# WAB_1x4_bus_transceivers.net
KiCad netlist of a schematic drawn in Altium Designer
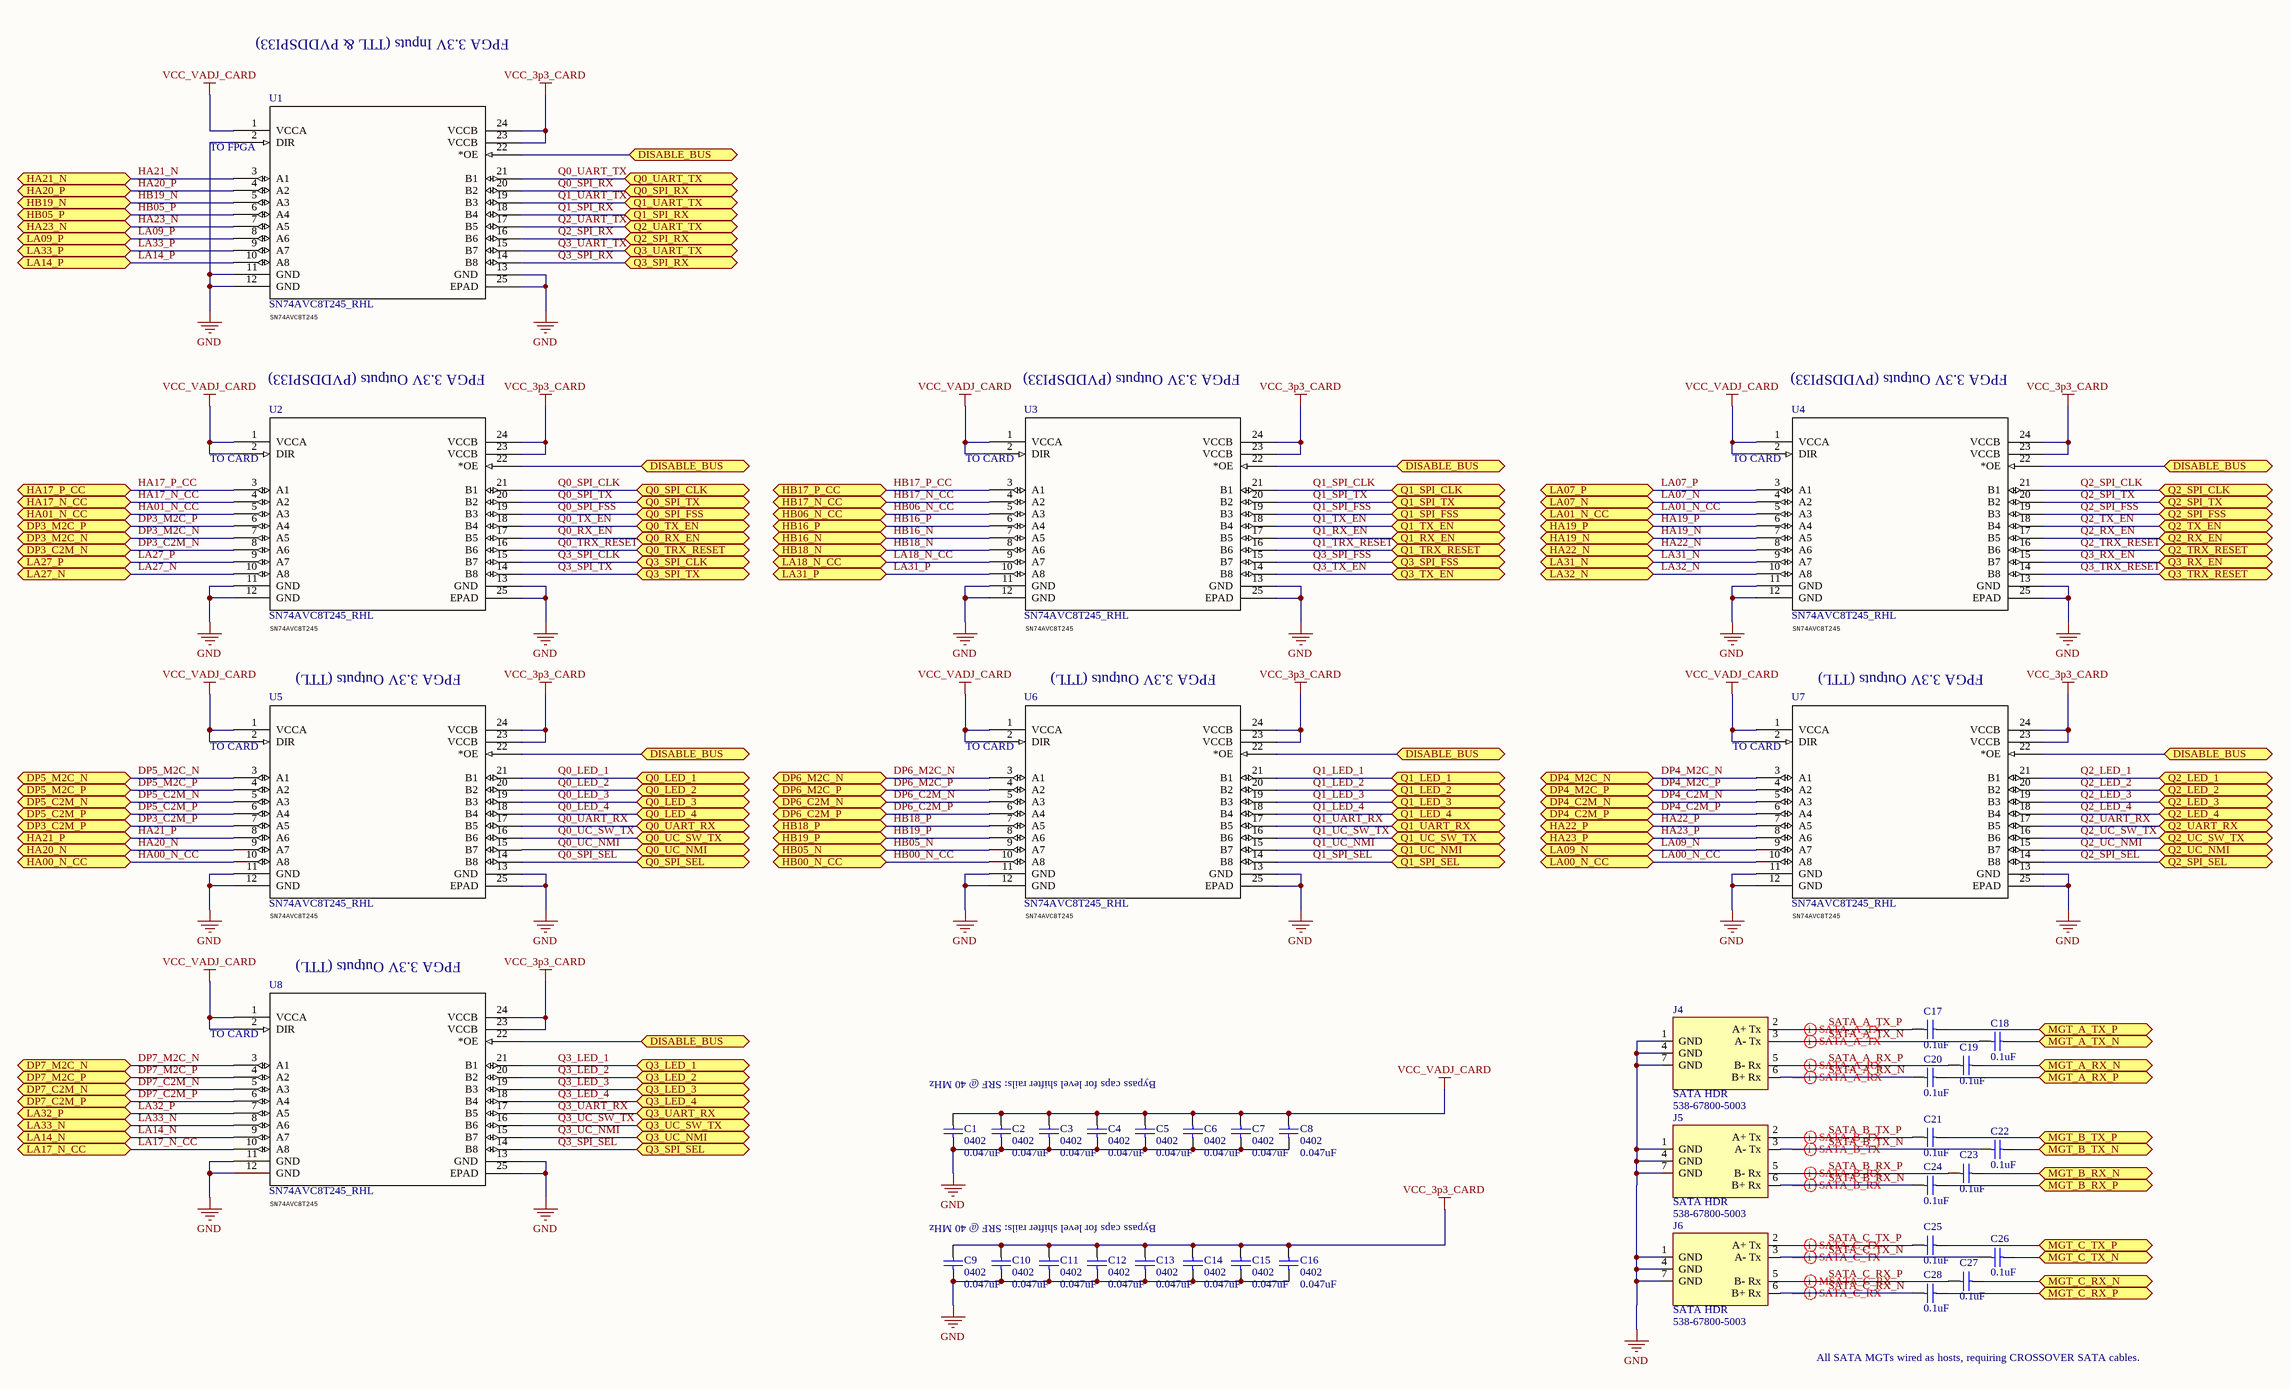
[diagram p0: WAB_1x4_bus_transceivers.SchDoc]

(export (version "E")
  (design (tool "Eeschema 10.0.6"))
  (components
    (comp (ref "C1")
      (value "0402")
      (footprint "0402_SMT_CAP")
      (description "0402 SMT Capacitor")
      (fields (field (name "ALTIUM_VALUE") "0.047uF"))
      (libsource (lib "RNG_Parts") (part "Cap_0402"))
    )
    (comp (ref "C2")
      (value "0402")
      (footprint "0402_SMT_CAP")
      (description "0402 SMT Capacitor")
      (fields (field (name "ALTIUM_VALUE") "0.047uF"))
      (libsource (lib "RNG_Parts") (part "Cap_0402"))
    )
    (comp (ref "C3")
      (value "0402")
      (footprint "0402_SMT_CAP")
      (description "0402 SMT Capacitor")
      (fields (field (name "ALTIUM_VALUE") "0.047uF"))
      (libsource (lib "RNG_Parts") (part "Cap_0402"))
    )
    (comp (ref "C4")
      (value "0402")
      (footprint "0402_SMT_CAP")
      (description "0402 SMT Capacitor")
      (fields (field (name "ALTIUM_VALUE") "0.047uF"))
      (libsource (lib "RNG_Parts") (part "Cap_0402"))
    )
    (comp (ref "C5")
      (value "0402")
      (footprint "0402_SMT_CAP")
      (description "0402 SMT Capacitor")
      (fields (field (name "ALTIUM_VALUE") "0.047uF"))
      (libsource (lib "RNG_Parts") (part "Cap_0402"))
    )
    (comp (ref "C6")
      (value "0402")
      (footprint "0402_SMT_CAP")
      (description "0402 SMT Capacitor")
      (fields (field (name "ALTIUM_VALUE") "0.047uF"))
      (libsource (lib "RNG_Parts") (part "Cap_0402"))
    )
    (comp (ref "C7")
      (value "0402")
      (footprint "0402_SMT_CAP")
      (description "0402 SMT Capacitor")
      (fields (field (name "ALTIUM_VALUE") "0.047uF"))
      (libsource (lib "RNG_Parts") (part "Cap_0402"))
    )
    (comp (ref "C8")
      (value "0402")
      (footprint "0402_SMT_CAP")
      (description "0402 SMT Capacitor")
      (fields (field (name "ALTIUM_VALUE") "0.047uF"))
      (libsource (lib "RNG_Parts") (part "Cap_0402"))
    )
    (comp (ref "C9")
      (value "0402")
      (footprint "0402_SMT_CAP")
      (description "0402 SMT Capacitor")
      (fields (field (name "ALTIUM_VALUE") "0.047uF"))
      (libsource (lib "RNG_Parts") (part "Cap_0402"))
    )
    (comp (ref "C10")
      (value "0402")
      (footprint "0402_SMT_CAP")
      (description "0402 SMT Capacitor")
      (fields (field (name "ALTIUM_VALUE") "0.047uF"))
      (libsource (lib "RNG_Parts") (part "Cap_0402"))
    )
    (comp (ref "C11")
      (value "0402")
      (footprint "0402_SMT_CAP")
      (description "0402 SMT Capacitor")
      (fields (field (name "ALTIUM_VALUE") "0.047uF"))
      (libsource (lib "RNG_Parts") (part "Cap_0402"))
    )
    (comp (ref "C12")
      (value "0402")
      (footprint "0402_SMT_CAP")
      (description "0402 SMT Capacitor")
      (fields (field (name "ALTIUM_VALUE") "0.047uF"))
      (libsource (lib "RNG_Parts") (part "Cap_0402"))
    )
    (comp (ref "C13")
      (value "0402")
      (footprint "0402_SMT_CAP")
      (description "0402 SMT Capacitor")
      (fields (field (name "ALTIUM_VALUE") "0.047uF"))
      (libsource (lib "RNG_Parts") (part "Cap_0402"))
    )
    (comp (ref "C14")
      (value "0402")
      (footprint "0402_SMT_CAP")
      (description "0402 SMT Capacitor")
      (fields (field (name "ALTIUM_VALUE") "0.047uF"))
      (libsource (lib "RNG_Parts") (part "Cap_0402"))
    )
    (comp (ref "C15")
      (value "0402")
      (footprint "0402_SMT_CAP")
      (description "0402 SMT Capacitor")
      (fields (field (name "ALTIUM_VALUE") "0.047uF"))
      (libsource (lib "RNG_Parts") (part "Cap_0402"))
    )
    (comp (ref "C16")
      (value "0402")
      (footprint "0402_SMT_CAP")
      (description "0402 SMT Capacitor")
      (fields (field (name "ALTIUM_VALUE") "0.047uF"))
      (libsource (lib "RNG_Parts") (part "Cap_0402"))
    )
    (comp (ref "C17")
      (value "0.1uF")
      (footprint "0402_SMT_CAP")
      (description "0402 SMT Capacitor")
      (fields (field (name "Comment") "0402"))
      (libsource (lib "RNG_Parts") (part "Cap_0402"))
    )
    (comp (ref "C18")
      (value "0.1uF")
      (footprint "0402_SMT_CAP")
      (description "0402 SMT Capacitor")
      (fields (field (name "Comment") "0402"))
      (libsource (lib "RNG_Parts") (part "Cap_0402"))
    )
    (comp (ref "C19")
      (value "0.1uF")
      (footprint "0402_SMT_CAP")
      (description "0402 SMT Capacitor")
      (fields (field (name "Comment") "0402"))
      (libsource (lib "RNG_Parts") (part "Cap_0402"))
    )
    (comp (ref "C20")
      (value "0.1uF")
      (footprint "0402_SMT_CAP")
      (description "0402 SMT Capacitor")
      (fields (field (name "Comment") "0402"))
      (libsource (lib "RNG_Parts") (part "Cap_0402"))
    )
    (comp (ref "C21")
      (value "0.1uF")
      (footprint "0402_SMT_CAP")
      (description "0402 SMT Capacitor")
      (fields (field (name "Comment") "0402"))
      (libsource (lib "RNG_Parts") (part "Cap_0402"))
    )
    (comp (ref "C22")
      (value "0.1uF")
      (footprint "0402_SMT_CAP")
      (description "0402 SMT Capacitor")
      (fields (field (name "Comment") "0402"))
      (libsource (lib "RNG_Parts") (part "Cap_0402"))
    )
    (comp (ref "C23")
      (value "0.1uF")
      (footprint "0402_SMT_CAP")
      (description "0402 SMT Capacitor")
      (fields (field (name "Comment") "0402"))
      (libsource (lib "RNG_Parts") (part "Cap_0402"))
    )
    (comp (ref "C24")
      (value "0.1uF")
      (footprint "0402_SMT_CAP")
      (description "0402 SMT Capacitor")
      (fields (field (name "Comment") "0402"))
      (libsource (lib "RNG_Parts") (part "Cap_0402"))
    )
    (comp (ref "C25")
      (value "0.1uF")
      (footprint "0402_SMT_CAP")
      (description "0402 SMT Capacitor")
      (fields (field (name "Comment") "0402"))
      (libsource (lib "RNG_Parts") (part "Cap_0402"))
    )
    (comp (ref "C26")
      (value "0.1uF")
      (footprint "0402_SMT_CAP")
      (description "0402 SMT Capacitor")
      (fields (field (name "Comment") "0402"))
      (libsource (lib "RNG_Parts") (part "Cap_0402"))
    )
    (comp (ref "C27")
      (value "0.1uF")
      (footprint "0402_SMT_CAP")
      (description "0402 SMT Capacitor")
      (fields (field (name "Comment") "0402"))
      (libsource (lib "RNG_Parts") (part "Cap_0402"))
    )
    (comp (ref "C28")
      (value "0.1uF")
      (footprint "0402_SMT_CAP")
      (description "0402 SMT Capacitor")
      (fields (field (name "Comment") "0402"))
      (libsource (lib "RNG_Parts") (part "Cap_0402"))
    )
    (comp (ref "J4")
      (value "SATA HDR")
      (footprint "Molex_67800-5003_V2")
      (description "Molex SMT SATA Jack, Shrouded, 67800-5003")
      (fields (field (name "SUPPLIER PART NUMBER 1") "538-67800-5003"))
      (libsource (lib "RNG_Parts") (part "SATA-SMT-Jack"))
    )
    (comp (ref "J5")
      (value "SATA HDR")
      (footprint "Molex_67800-5003_V2")
      (description "Molex SMT SATA Jack, Shrouded, 67800-5003")
      (fields (field (name "SUPPLIER PART NUMBER 1") "538-67800-5003"))
      (libsource (lib "RNG_Parts") (part "SATA-SMT-Jack"))
    )
    (comp (ref "J6")
      (value "SATA HDR")
      (footprint "Molex_67800-5003_V2")
      (description "Molex SMT SATA Jack, Shrouded, 67800-5003")
      (fields (field (name "SUPPLIER PART NUMBER 1") "538-67800-5003"))
      (libsource (lib "RNG_Parts") (part "SATA-SMT-Jack"))
    )
    (comp (ref "U1")
      (value "SN74AVC8T245_RHL")
      (footprint "RHL24_4P05X2P05_V3")
      (description "8-Bit Dual-Supply Bus Transceiver QFN 320 Mbps")
      (fields
        (field (name "MANUFACTURER") "Texas Instruments")
        (field (name "GENERIC_PART_NUMBER") "SN74AVC8T245")
        (field (name "MANUFACTURER_PART_NUMBER") "sn74avc8t245_rhl_24")
      )
      (libsource (lib "RNG_Parts") (part "SN74AVC8T245_RHL"))
    )
    (comp (ref "U2")
      (value "SN74AVC8T245_RHL")
      (footprint "RHL24_4P05X2P05_V3")
      (description "8-Bit Dual-Supply Bus Transceiver QFN 320 Mbps")
      (fields
        (field (name "MANUFACTURER") "Texas Instruments")
        (field (name "GENERIC_PART_NUMBER") "SN74AVC8T245")
        (field (name "MANUFACTURER_PART_NUMBER") "sn74avc8t245_rhl_24")
      )
      (libsource (lib "RNG_Parts") (part "SN74AVC8T245_RHL"))
    )
    (comp (ref "U3")
      (value "SN74AVC8T245_RHL")
      (footprint "RHL24_4P05X2P05_V3")
      (description "8-Bit Dual-Supply Bus Transceiver QFN 320 Mbps")
      (fields
        (field (name "MANUFACTURER") "Texas Instruments")
        (field (name "GENERIC_PART_NUMBER") "SN74AVC8T245")
        (field (name "MANUFACTURER_PART_NUMBER") "sn74avc8t245_rhl_24")
      )
      (libsource (lib "RNG_Parts") (part "SN74AVC8T245_RHL"))
    )
    (comp (ref "U4")
      (value "SN74AVC8T245_RHL")
      (footprint "RHL24_4P05X2P05_V3")
      (description "8-Bit Dual-Supply Bus Transceiver QFN 320 Mbps")
      (fields
        (field (name "MANUFACTURER") "Texas Instruments")
        (field (name "GENERIC_PART_NUMBER") "SN74AVC8T245")
        (field (name "MANUFACTURER_PART_NUMBER") "sn74avc8t245_rhl_24")
      )
      (libsource (lib "RNG_Parts") (part "SN74AVC8T245_RHL"))
    )
    (comp (ref "U5")
      (value "SN74AVC8T245_RHL")
      (footprint "RHL24_4P05X2P05_V3")
      (description "8-Bit Dual-Supply Bus Transceiver QFN 320 Mbps")
      (fields
        (field (name "MANUFACTURER") "Texas Instruments")
        (field (name "GENERIC_PART_NUMBER") "SN74AVC8T245")
        (field (name "MANUFACTURER_PART_NUMBER") "sn74avc8t245_rhl_24")
      )
      (libsource (lib "RNG_Parts") (part "SN74AVC8T245_RHL"))
    )
    (comp (ref "U6")
      (value "SN74AVC8T245_RHL")
      (footprint "RHL24_4P05X2P05_V3")
      (description "8-Bit Dual-Supply Bus Transceiver QFN 320 Mbps")
      (fields
        (field (name "MANUFACTURER") "Texas Instruments")
        (field (name "GENERIC_PART_NUMBER") "SN74AVC8T245")
        (field (name "MANUFACTURER_PART_NUMBER") "sn74avc8t245_rhl_24")
      )
      (libsource (lib "RNG_Parts") (part "SN74AVC8T245_RHL"))
    )
    (comp (ref "U7")
      (value "SN74AVC8T245_RHL")
      (footprint "RHL24_4P05X2P05_V3")
      (description "8-Bit Dual-Supply Bus Transceiver QFN 320 Mbps")
      (fields
        (field (name "MANUFACTURER") "Texas Instruments")
        (field (name "GENERIC_PART_NUMBER") "SN74AVC8T245")
        (field (name "MANUFACTURER_PART_NUMBER") "sn74avc8t245_rhl_24")
      )
      (libsource (lib "RNG_Parts") (part "SN74AVC8T245_RHL"))
    )
    (comp (ref "U8")
      (value "SN74AVC8T245_RHL")
      (footprint "RHL24_4P05X2P05_V3")
      (description "8-Bit Dual-Supply Bus Transceiver QFN 320 Mbps")
      (fields
        (field (name "MANUFACTURER") "Texas Instruments")
        (field (name "GENERIC_PART_NUMBER") "SN74AVC8T245")
        (field (name "MANUFACTURER_PART_NUMBER") "sn74avc8t245_rhl_24")
      )
      (libsource (lib "RNG_Parts") (part "SN74AVC8T245_RHL"))
    )
  )
  (nets
    (net (code "1") (name "/DISABLE_BUS") (class "Default")
      (node (ref "U1") (pin "22") (pinfunction "*OE_22") (pintype "input"))
      (node (ref "U2") (pin "22") (pinfunction "*OE_22") (pintype "input"))
      (node (ref "U3") (pin "22") (pinfunction "*OE_22") (pintype "input"))
      (node (ref "U4") (pin "22") (pinfunction "*OE_22") (pintype "input"))
      (node (ref "U5") (pin "22") (pinfunction "*OE_22") (pintype "input"))
      (node (ref "U6") (pin "22") (pinfunction "*OE_22") (pintype "input"))
      (node (ref "U7") (pin "22") (pinfunction "*OE_22") (pintype "input"))
      (node (ref "U8") (pin "22") (pinfunction "*OE_22") (pintype "input"))
    )
    (net (code "2") (name "/DP3_C2M_N") (class "Default")
      (node (ref "U2") (pin "8") (pinfunction "A6_8") (pintype "bidirectional"))
    )
    (net (code "3") (name "/DP3_C2M_P") (class "Default")
      (node (ref "U5") (pin "7") (pinfunction "A5_7") (pintype "bidirectional"))
    )
    (net (code "4") (name "/DP3_M2C_N") (class "Default")
      (node (ref "U2") (pin "7") (pinfunction "A5_7") (pintype "bidirectional"))
    )
    (net (code "5") (name "/DP3_M2C_P") (class "Default")
      (node (ref "U2") (pin "6") (pinfunction "A4_6") (pintype "bidirectional"))
    )
    (net (code "6") (name "/DP4_C2M_N") (class "Default")
      (node (ref "U7") (pin "5") (pinfunction "A3_5") (pintype "bidirectional"))
    )
    (net (code "7") (name "/DP4_C2M_P") (class "Default")
      (node (ref "U7") (pin "6") (pinfunction "A4_6") (pintype "bidirectional"))
    )
    (net (code "8") (name "/DP4_M2C_N") (class "Default")
      (node (ref "U7") (pin "3") (pinfunction "A1_3") (pintype "bidirectional"))
    )
    (net (code "9") (name "/DP4_M2C_P") (class "Default")
      (node (ref "U7") (pin "4") (pinfunction "A2_4") (pintype "bidirectional"))
    )
    (net (code "10") (name "/DP5_C2M_N") (class "Default")
      (node (ref "U5") (pin "5") (pinfunction "A3_5") (pintype "bidirectional"))
    )
    (net (code "11") (name "/DP5_C2M_P") (class "Default")
      (node (ref "U5") (pin "6") (pinfunction "A4_6") (pintype "bidirectional"))
    )
    (net (code "12") (name "/DP5_M2C_N") (class "Default")
      (node (ref "U5") (pin "3") (pinfunction "A1_3") (pintype "bidirectional"))
    )
    (net (code "13") (name "/DP5_M2C_P") (class "Default")
      (node (ref "U5") (pin "4") (pinfunction "A2_4") (pintype "bidirectional"))
    )
    (net (code "14") (name "/DP6_C2M_N") (class "Default")
      (node (ref "U6") (pin "5") (pinfunction "A3_5") (pintype "bidirectional"))
    )
    (net (code "15") (name "/DP6_C2M_P") (class "Default")
      (node (ref "U6") (pin "6") (pinfunction "A4_6") (pintype "bidirectional"))
    )
    (net (code "16") (name "/DP6_M2C_N") (class "Default")
      (node (ref "U6") (pin "3") (pinfunction "A1_3") (pintype "bidirectional"))
    )
    (net (code "17") (name "/DP6_M2C_P") (class "Default")
      (node (ref "U6") (pin "4") (pinfunction "A2_4") (pintype "bidirectional"))
    )
    (net (code "18") (name "/DP7_C2M_N") (class "Default")
      (node (ref "U8") (pin "5") (pinfunction "A3_5") (pintype "bidirectional"))
    )
    (net (code "19") (name "/DP7_C2M_P") (class "Default")
      (node (ref "U8") (pin "6") (pinfunction "A4_6") (pintype "bidirectional"))
    )
    (net (code "20") (name "/DP7_M2C_N") (class "Default")
      (node (ref "U8") (pin "3") (pinfunction "A1_3") (pintype "bidirectional"))
    )
    (net (code "21") (name "/DP7_M2C_P") (class "Default")
      (node (ref "U8") (pin "4") (pinfunction "A2_4") (pintype "bidirectional"))
    )
    (net (code "22") (name "/HA00_N_CC") (class "Default")
      (node (ref "U5") (pin "10") (pinfunction "A8_10") (pintype "bidirectional"))
    )
    (net (code "23") (name "/HA01_N_CC") (class "Default")
      (node (ref "U2") (pin "5") (pinfunction "A3_5") (pintype "bidirectional"))
    )
    (net (code "24") (name "/HA17_N_CC") (class "Default")
      (node (ref "U2") (pin "4") (pinfunction "A2_4") (pintype "bidirectional"))
    )
    (net (code "25") (name "/HA17_P_CC") (class "Default")
      (node (ref "U2") (pin "3") (pinfunction "A1_3") (pintype "bidirectional"))
    )
    (net (code "26") (name "/HA19_N") (class "Default")
      (node (ref "U4") (pin "7") (pinfunction "A5_7") (pintype "bidirectional"))
    )
    (net (code "27") (name "/HA19_P") (class "Default")
      (node (ref "U4") (pin "6") (pinfunction "A4_6") (pintype "bidirectional"))
    )
    (net (code "28") (name "/HA20_N") (class "Default")
      (node (ref "U5") (pin "9") (pinfunction "A7_9") (pintype "bidirectional"))
    )
    (net (code "29") (name "/HA20_P") (class "Default")
      (node (ref "U1") (pin "4") (pinfunction "A2_4") (pintype "bidirectional"))
    )
    (net (code "30") (name "/HA21_N") (class "Default")
      (node (ref "U1") (pin "3") (pinfunction "A1_3") (pintype "bidirectional"))
    )
    (net (code "31") (name "/HA21_P") (class "Default")
      (node (ref "U5") (pin "8") (pinfunction "A6_8") (pintype "bidirectional"))
    )
    (net (code "32") (name "/HA22_N") (class "Default")
      (node (ref "U4") (pin "8") (pinfunction "A6_8") (pintype "bidirectional"))
    )
    (net (code "33") (name "/HA22_P") (class "Default")
      (node (ref "U7") (pin "7") (pinfunction "A5_7") (pintype "bidirectional"))
    )
    (net (code "34") (name "/HA23_N") (class "Default")
      (node (ref "U1") (pin "7") (pinfunction "A5_7") (pintype "bidirectional"))
    )
    (net (code "35") (name "/HA23_P") (class "Default")
      (node (ref "U7") (pin "8") (pinfunction "A6_8") (pintype "bidirectional"))
    )
    (net (code "36") (name "/HB00_N_CC") (class "Default")
      (node (ref "U6") (pin "10") (pinfunction "A8_10") (pintype "bidirectional"))
    )
    (net (code "37") (name "/HB05_N") (class "Default")
      (node (ref "U6") (pin "9") (pinfunction "A7_9") (pintype "bidirectional"))
    )
    (net (code "38") (name "/HB05_P") (class "Default")
      (node (ref "U1") (pin "6") (pinfunction "A4_6") (pintype "bidirectional"))
    )
    (net (code "39") (name "/HB06_N_CC") (class "Default")
      (node (ref "U3") (pin "5") (pinfunction "A3_5") (pintype "bidirectional"))
    )
    (net (code "40") (name "/HB16_N") (class "Default")
      (node (ref "U3") (pin "7") (pinfunction "A5_7") (pintype "bidirectional"))
    )
    (net (code "41") (name "/HB16_P") (class "Default")
      (node (ref "U3") (pin "6") (pinfunction "A4_6") (pintype "bidirectional"))
    )
    (net (code "42") (name "/HB17_N_CC") (class "Default")
      (node (ref "U3") (pin "4") (pinfunction "A2_4") (pintype "bidirectional"))
    )
    (net (code "43") (name "/HB17_P_CC") (class "Default")
      (node (ref "U3") (pin "3") (pinfunction "A1_3") (pintype "bidirectional"))
    )
    (net (code "44") (name "/HB18_N") (class "Default")
      (node (ref "U3") (pin "8") (pinfunction "A6_8") (pintype "bidirectional"))
    )
    (net (code "45") (name "/HB18_P") (class "Default")
      (node (ref "U6") (pin "7") (pinfunction "A5_7") (pintype "bidirectional"))
    )
    (net (code "46") (name "/HB19_N") (class "Default")
      (node (ref "U1") (pin "5") (pinfunction "A3_5") (pintype "bidirectional"))
    )
    (net (code "47") (name "/HB19_P") (class "Default")
      (node (ref "U6") (pin "8") (pinfunction "A6_8") (pintype "bidirectional"))
    )
    (net (code "48") (name "/LA00_N_CC") (class "Default")
      (node (ref "U7") (pin "10") (pinfunction "A8_10") (pintype "bidirectional"))
    )
    (net (code "49") (name "/LA01_N_CC") (class "Default")
      (node (ref "U4") (pin "5") (pinfunction "A3_5") (pintype "bidirectional"))
    )
    (net (code "50") (name "/LA07_N") (class "Default")
      (node (ref "U4") (pin "4") (pinfunction "A2_4") (pintype "bidirectional"))
    )
    (net (code "51") (name "/LA07_P") (class "Default")
      (node (ref "U4") (pin "3") (pinfunction "A1_3") (pintype "bidirectional"))
    )
    (net (code "52") (name "/LA09_N") (class "Default")
      (node (ref "U7") (pin "9") (pinfunction "A7_9") (pintype "bidirectional"))
    )
    (net (code "53") (name "/LA09_P") (class "Default")
      (node (ref "U1") (pin "8") (pinfunction "A6_8") (pintype "bidirectional"))
    )
    (net (code "54") (name "/LA14_N") (class "Default")
      (node (ref "U8") (pin "9") (pinfunction "A7_9") (pintype "bidirectional"))
    )
    (net (code "55") (name "/LA14_P") (class "Default")
      (node (ref "U1") (pin "10") (pinfunction "A8_10") (pintype "bidirectional"))
    )
    (net (code "56") (name "/LA17_N_CC") (class "Default")
      (node (ref "U8") (pin "10") (pinfunction "A8_10") (pintype "bidirectional"))
    )
    (net (code "57") (name "/LA18_N_CC") (class "Default")
      (node (ref "U3") (pin "9") (pinfunction "A7_9") (pintype "bidirectional"))
    )
    (net (code "58") (name "/LA27_N") (class "Default")
      (node (ref "U2") (pin "10") (pinfunction "A8_10") (pintype "bidirectional"))
    )
    (net (code "59") (name "/LA27_P") (class "Default")
      (node (ref "U2") (pin "9") (pinfunction "A7_9") (pintype "bidirectional"))
    )
    (net (code "60") (name "/LA31_N") (class "Default")
      (node (ref "U4") (pin "9") (pinfunction "A7_9") (pintype "bidirectional"))
    )
    (net (code "61") (name "/LA31_P") (class "Default")
      (node (ref "U3") (pin "10") (pinfunction "A8_10") (pintype "bidirectional"))
    )
    (net (code "62") (name "/LA32_N") (class "Default")
      (node (ref "U4") (pin "10") (pinfunction "A8_10") (pintype "bidirectional"))
    )
    (net (code "63") (name "/LA32_P") (class "Default")
      (node (ref "U8") (pin "7") (pinfunction "A5_7") (pintype "bidirectional"))
    )
    (net (code "64") (name "/LA33_N") (class "Default")
      (node (ref "U8") (pin "8") (pinfunction "A6_8") (pintype "bidirectional"))
    )
    (net (code "65") (name "/LA33_P") (class "Default")
      (node (ref "U1") (pin "9") (pinfunction "A7_9") (pintype "bidirectional"))
    )
    (net (code "66") (name "/MGT_A_RX_N") (class "Default")
      (node (ref "C19") (pin "2") (pinfunction "2_2") (pintype "passive"))
    )
    (net (code "67") (name "/MGT_A_RX_P") (class "Default")
      (node (ref "C20") (pin "2") (pinfunction "2_2") (pintype "passive"))
    )
    (net (code "68") (name "/MGT_A_TX_N") (class "Default")
      (node (ref "C18") (pin "2") (pinfunction "2_2") (pintype "passive"))
    )
    (net (code "69") (name "/MGT_A_TX_P") (class "Default")
      (node (ref "C17") (pin "2") (pinfunction "2_2") (pintype "passive"))
    )
    (net (code "70") (name "/MGT_B_RX_N") (class "Default")
      (node (ref "C23") (pin "2") (pinfunction "2_2") (pintype "passive"))
    )
    (net (code "71") (name "/MGT_B_RX_P") (class "Default")
      (node (ref "C24") (pin "2") (pinfunction "2_2") (pintype "passive"))
    )
    (net (code "72") (name "/MGT_B_TX_N") (class "Default")
      (node (ref "C22") (pin "2") (pinfunction "2_2") (pintype "passive"))
    )
    (net (code "73") (name "/MGT_B_TX_P") (class "Default")
      (node (ref "C21") (pin "2") (pinfunction "2_2") (pintype "passive"))
    )
    (net (code "74") (name "/MGT_C_RX_N") (class "Default")
      (node (ref "C27") (pin "2") (pinfunction "2_2") (pintype "passive"))
    )
    (net (code "75") (name "/MGT_C_RX_P") (class "Default")
      (node (ref "C28") (pin "2") (pinfunction "2_2") (pintype "passive"))
    )
    (net (code "76") (name "/MGT_C_TX_N") (class "Default")
      (node (ref "C26") (pin "2") (pinfunction "2_2") (pintype "passive"))
    )
    (net (code "77") (name "/MGT_C_TX_P") (class "Default")
      (node (ref "C25") (pin "2") (pinfunction "2_2") (pintype "passive"))
    )
    (net (code "78") (name "/Q0_LED_1") (class "Default")
      (node (ref "U5") (pin "21") (pinfunction "B1_21") (pintype "bidirectional"))
    )
    (net (code "79") (name "/Q0_LED_2") (class "Default")
      (node (ref "U5") (pin "20") (pinfunction "B2_20") (pintype "bidirectional"))
    )
    (net (code "80") (name "/Q0_LED_3") (class "Default")
      (node (ref "U5") (pin "19") (pinfunction "B3_19") (pintype "bidirectional"))
    )
    (net (code "81") (name "/Q0_LED_4") (class "Default")
      (node (ref "U5") (pin "18") (pinfunction "B4_18") (pintype "bidirectional"))
    )
    (net (code "82") (name "/Q0_RX_EN") (class "Default")
      (node (ref "U2") (pin "17") (pinfunction "B5_17") (pintype "bidirectional"))
    )
    (net (code "83") (name "/Q0_SPI_CLK") (class "Default")
      (node (ref "U2") (pin "21") (pinfunction "B1_21") (pintype "bidirectional"))
    )
    (net (code "84") (name "/Q0_SPI_FSS") (class "Default")
      (node (ref "U2") (pin "19") (pinfunction "B3_19") (pintype "bidirectional"))
    )
    (net (code "85") (name "/Q0_SPI_RX") (class "Default")
      (node (ref "U1") (pin "20") (pinfunction "B2_20") (pintype "bidirectional"))
    )
    (net (code "86") (name "/Q0_SPI_SEL") (class "Default")
      (node (ref "U5") (pin "14") (pinfunction "B8_14") (pintype "bidirectional"))
    )
    (net (code "87") (name "/Q0_SPI_TX") (class "Default")
      (node (ref "U2") (pin "20") (pinfunction "B2_20") (pintype "bidirectional"))
    )
    (net (code "88") (name "/Q0_TRX_RESET") (class "Default")
      (node (ref "U2") (pin "16") (pinfunction "B6_16") (pintype "bidirectional"))
    )
    (net (code "89") (name "/Q0_TX_EN") (class "Default")
      (node (ref "U2") (pin "18") (pinfunction "B4_18") (pintype "bidirectional"))
    )
    (net (code "90") (name "/Q0_UART_RX") (class "Default")
      (node (ref "U5") (pin "17") (pinfunction "B5_17") (pintype "bidirectional"))
    )
    (net (code "91") (name "/Q0_UART_TX") (class "Default")
      (node (ref "U1") (pin "21") (pinfunction "B1_21") (pintype "bidirectional"))
    )
    (net (code "92") (name "/Q0_UC_NMI") (class "Default")
      (node (ref "U5") (pin "15") (pinfunction "B7_15") (pintype "bidirectional"))
    )
    (net (code "93") (name "/Q0_UC_SW_TX") (class "Default")
      (node (ref "U5") (pin "16") (pinfunction "B6_16") (pintype "bidirectional"))
    )
    (net (code "94") (name "/Q1_LED_1") (class "Default")
      (node (ref "U6") (pin "21") (pinfunction "B1_21") (pintype "bidirectional"))
    )
    (net (code "95") (name "/Q1_LED_2") (class "Default")
      (node (ref "U6") (pin "20") (pinfunction "B2_20") (pintype "bidirectional"))
    )
    (net (code "96") (name "/Q1_LED_3") (class "Default")
      (node (ref "U6") (pin "19") (pinfunction "B3_19") (pintype "bidirectional"))
    )
    (net (code "97") (name "/Q1_LED_4") (class "Default")
      (node (ref "U6") (pin "18") (pinfunction "B4_18") (pintype "bidirectional"))
    )
    (net (code "98") (name "/Q1_RX_EN") (class "Default")
      (node (ref "U3") (pin "17") (pinfunction "B5_17") (pintype "bidirectional"))
    )
    (net (code "99") (name "/Q1_SPI_CLK") (class "Default")
      (node (ref "U3") (pin "21") (pinfunction "B1_21") (pintype "bidirectional"))
    )
    (net (code "100") (name "/Q1_SPI_FSS") (class "Default")
      (node (ref "U3") (pin "19") (pinfunction "B3_19") (pintype "bidirectional"))
    )
    (net (code "101") (name "/Q1_SPI_RX") (class "Default")
      (node (ref "U1") (pin "18") (pinfunction "B4_18") (pintype "bidirectional"))
    )
    (net (code "102") (name "/Q1_SPI_SEL") (class "Default")
      (node (ref "U6") (pin "14") (pinfunction "B8_14") (pintype "bidirectional"))
    )
    (net (code "103") (name "/Q1_SPI_TX") (class "Default")
      (node (ref "U3") (pin "20") (pinfunction "B2_20") (pintype "bidirectional"))
    )
    (net (code "104") (name "/Q1_TRX_RESET") (class "Default")
      (node (ref "U3") (pin "16") (pinfunction "B6_16") (pintype "bidirectional"))
    )
    (net (code "105") (name "/Q1_TX_EN") (class "Default")
      (node (ref "U3") (pin "18") (pinfunction "B4_18") (pintype "bidirectional"))
    )
    (net (code "106") (name "/Q1_UART_RX") (class "Default")
      (node (ref "U6") (pin "17") (pinfunction "B5_17") (pintype "bidirectional"))
    )
    (net (code "107") (name "/Q1_UART_TX") (class "Default")
      (node (ref "U1") (pin "19") (pinfunction "B3_19") (pintype "bidirectional"))
    )
    (net (code "108") (name "/Q1_UC_NMI") (class "Default")
      (node (ref "U6") (pin "15") (pinfunction "B7_15") (pintype "bidirectional"))
    )
    (net (code "109") (name "/Q1_UC_SW_TX") (class "Default")
      (node (ref "U6") (pin "16") (pinfunction "B6_16") (pintype "bidirectional"))
    )
    (net (code "110") (name "/Q2_LED_1") (class "Default")
      (node (ref "U7") (pin "21") (pinfunction "B1_21") (pintype "bidirectional"))
    )
    (net (code "111") (name "/Q2_LED_2") (class "Default")
      (node (ref "U7") (pin "20") (pinfunction "B2_20") (pintype "bidirectional"))
    )
    (net (code "112") (name "/Q2_LED_3") (class "Default")
      (node (ref "U7") (pin "19") (pinfunction "B3_19") (pintype "bidirectional"))
    )
    (net (code "113") (name "/Q2_LED_4") (class "Default")
      (node (ref "U7") (pin "18") (pinfunction "B4_18") (pintype "bidirectional"))
    )
    (net (code "114") (name "/Q2_RX_EN") (class "Default")
      (node (ref "U4") (pin "17") (pinfunction "B5_17") (pintype "bidirectional"))
    )
    (net (code "115") (name "/Q2_SPI_CLK") (class "Default")
      (node (ref "U4") (pin "21") (pinfunction "B1_21") (pintype "bidirectional"))
    )
    (net (code "116") (name "/Q2_SPI_FSS") (class "Default")
      (node (ref "U4") (pin "19") (pinfunction "B3_19") (pintype "bidirectional"))
    )
    (net (code "117") (name "/Q2_SPI_RX") (class "Default")
      (node (ref "U1") (pin "16") (pinfunction "B6_16") (pintype "bidirectional"))
    )
    (net (code "118") (name "/Q2_SPI_SEL") (class "Default")
      (node (ref "U7") (pin "14") (pinfunction "B8_14") (pintype "bidirectional"))
    )
    (net (code "119") (name "/Q2_SPI_TX") (class "Default")
      (node (ref "U4") (pin "20") (pinfunction "B2_20") (pintype "bidirectional"))
    )
    (net (code "120") (name "/Q2_TRX_RESET") (class "Default")
      (node (ref "U4") (pin "16") (pinfunction "B6_16") (pintype "bidirectional"))
    )
    (net (code "121") (name "/Q2_TX_EN") (class "Default")
      (node (ref "U4") (pin "18") (pinfunction "B4_18") (pintype "bidirectional"))
    )
    (net (code "122") (name "/Q2_UART_RX") (class "Default")
      (node (ref "U7") (pin "17") (pinfunction "B5_17") (pintype "bidirectional"))
    )
    (net (code "123") (name "/Q2_UART_TX") (class "Default")
      (node (ref "U1") (pin "17") (pinfunction "B5_17") (pintype "bidirectional"))
    )
    (net (code "124") (name "/Q2_UC_NMI") (class "Default")
      (node (ref "U7") (pin "15") (pinfunction "B7_15") (pintype "bidirectional"))
    )
    (net (code "125") (name "/Q2_UC_SW_TX") (class "Default")
      (node (ref "U7") (pin "16") (pinfunction "B6_16") (pintype "bidirectional"))
    )
    (net (code "126") (name "/Q3_LED_1") (class "Default")
      (node (ref "U8") (pin "21") (pinfunction "B1_21") (pintype "bidirectional"))
    )
    (net (code "127") (name "/Q3_LED_2") (class "Default")
      (node (ref "U8") (pin "20") (pinfunction "B2_20") (pintype "bidirectional"))
    )
    (net (code "128") (name "/Q3_LED_3") (class "Default")
      (node (ref "U8") (pin "19") (pinfunction "B3_19") (pintype "bidirectional"))
    )
    (net (code "129") (name "/Q3_LED_4") (class "Default")
      (node (ref "U8") (pin "18") (pinfunction "B4_18") (pintype "bidirectional"))
    )
    (net (code "130") (name "/Q3_RX_EN") (class "Default")
      (node (ref "U4") (pin "15") (pinfunction "B7_15") (pintype "bidirectional"))
    )
    (net (code "131") (name "/Q3_SPI_CLK") (class "Default")
      (node (ref "U2") (pin "15") (pinfunction "B7_15") (pintype "bidirectional"))
    )
    (net (code "132") (name "/Q3_SPI_FSS") (class "Default")
      (node (ref "U3") (pin "15") (pinfunction "B7_15") (pintype "bidirectional"))
    )
    (net (code "133") (name "/Q3_SPI_RX") (class "Default")
      (node (ref "U1") (pin "14") (pinfunction "B8_14") (pintype "bidirectional"))
    )
    (net (code "134") (name "/Q3_SPI_SEL") (class "Default")
      (node (ref "U8") (pin "14") (pinfunction "B8_14") (pintype "bidirectional"))
    )
    (net (code "135") (name "/Q3_SPI_TX") (class "Default")
      (node (ref "U2") (pin "14") (pinfunction "B8_14") (pintype "bidirectional"))
    )
    (net (code "136") (name "/Q3_TRX_RESET") (class "Default")
      (node (ref "U4") (pin "14") (pinfunction "B8_14") (pintype "bidirectional"))
    )
    (net (code "137") (name "/Q3_TX_EN") (class "Default")
      (node (ref "U3") (pin "14") (pinfunction "B8_14") (pintype "bidirectional"))
    )
    (net (code "138") (name "/Q3_UART_RX") (class "Default")
      (node (ref "U8") (pin "17") (pinfunction "B5_17") (pintype "bidirectional"))
    )
    (net (code "139") (name "/Q3_UART_TX") (class "Default")
      (node (ref "U1") (pin "15") (pinfunction "B7_15") (pintype "bidirectional"))
    )
    (net (code "140") (name "/Q3_UC_NMI") (class "Default")
      (node (ref "U8") (pin "15") (pinfunction "B7_15") (pintype "bidirectional"))
    )
    (net (code "141") (name "/Q3_UC_SW_TX") (class "Default")
      (node (ref "U8") (pin "16") (pinfunction "B6_16") (pintype "bidirectional"))
    )
    (net (code "142") (name "/SATA_A_RX_N") (class "Default")
      (node (ref "C20") (pin "1") (pinfunction "1_1") (pintype "passive"))
      (node (ref "J4") (pin "6") (pinfunction "B+_Rx_6") (pintype "power_in"))
    )
    (net (code "143") (name "/SATA_A_RX_P") (class "Default")
      (node (ref "C19") (pin "1") (pinfunction "1_1") (pintype "passive"))
      (node (ref "J4") (pin "5") (pinfunction "B-_Rx_5") (pintype "power_in"))
    )
    (net (code "144") (name "/SATA_A_TX_N") (class "Default")
      (node (ref "C18") (pin "1") (pinfunction "1_1") (pintype "passive"))
      (node (ref "J4") (pin "3") (pinfunction "A-_Tx_3") (pintype "power_in"))
    )
    (net (code "145") (name "/SATA_A_TX_P") (class "Default")
      (node (ref "C17") (pin "1") (pinfunction "1_1") (pintype "passive"))
      (node (ref "J4") (pin "2") (pinfunction "A+_Tx_2") (pintype "power_in"))
    )
    (net (code "146") (name "/SATA_B_RX_N") (class "Default")
      (node (ref "C24") (pin "1") (pinfunction "1_1") (pintype "passive"))
      (node (ref "J5") (pin "6") (pinfunction "B+_Rx_6") (pintype "power_in"))
    )
    (net (code "147") (name "/SATA_B_RX_P") (class "Default")
      (node (ref "C23") (pin "1") (pinfunction "1_1") (pintype "passive"))
      (node (ref "J5") (pin "5") (pinfunction "B-_Rx_5") (pintype "power_in"))
    )
    (net (code "148") (name "/SATA_B_TX_N") (class "Default")
      (node (ref "C22") (pin "1") (pinfunction "1_1") (pintype "passive"))
      (node (ref "J5") (pin "3") (pinfunction "A-_Tx_3") (pintype "power_in"))
    )
    (net (code "149") (name "/SATA_B_TX_P") (class "Default")
      (node (ref "C21") (pin "1") (pinfunction "1_1") (pintype "passive"))
      (node (ref "J5") (pin "2") (pinfunction "A+_Tx_2") (pintype "power_in"))
    )
    (net (code "150") (name "/SATA_C_RX_N") (class "Default")
      (node (ref "C28") (pin "1") (pinfunction "1_1") (pintype "passive"))
      (node (ref "J6") (pin "6") (pinfunction "B+_Rx_6") (pintype "power_in"))
    )
    (net (code "151") (name "/SATA_C_RX_P") (class "Default")
      (node (ref "C27") (pin "1") (pinfunction "1_1") (pintype "passive"))
      (node (ref "J6") (pin "5") (pinfunction "B-_Rx_5") (pintype "power_in"))
    )
    (net (code "152") (name "/SATA_C_TX_N") (class "Default")
      (node (ref "C26") (pin "1") (pinfunction "1_1") (pintype "passive"))
      (node (ref "J6") (pin "3") (pinfunction "A-_Tx_3") (pintype "power_in"))
    )
    (net (code "153") (name "/SATA_C_TX_P") (class "Default")
      (node (ref "C25") (pin "1") (pinfunction "1_1") (pintype "passive"))
      (node (ref "J6") (pin "2") (pinfunction "A+_Tx_2") (pintype "power_in"))
    )
    (net (code "154") (name "GND") (class "Default")
      (node (ref "C1") (pin "2") (pinfunction "2_2") (pintype "passive"))
      (node (ref "C10") (pin "2") (pinfunction "2_2") (pintype "passive"))
      (node (ref "C11") (pin "2") (pinfunction "2_2") (pintype "passive"))
      (node (ref "C12") (pin "2") (pinfunction "2_2") (pintype "passive"))
      (node (ref "C13") (pin "2") (pinfunction "2_2") (pintype "passive"))
      (node (ref "C14") (pin "2") (pinfunction "2_2") (pintype "passive"))
      (node (ref "C15") (pin "2") (pinfunction "2_2") (pintype "passive"))
      (node (ref "C16") (pin "2") (pinfunction "2_2") (pintype "passive"))
      (node (ref "C2") (pin "2") (pinfunction "2_2") (pintype "passive"))
      (node (ref "C3") (pin "2") (pinfunction "2_2") (pintype "passive"))
      (node (ref "C4") (pin "2") (pinfunction "2_2") (pintype "passive"))
      (node (ref "C5") (pin "2") (pinfunction "2_2") (pintype "passive"))
      (node (ref "C6") (pin "2") (pinfunction "2_2") (pintype "passive"))
      (node (ref "C7") (pin "2") (pinfunction "2_2") (pintype "passive"))
      (node (ref "C8") (pin "2") (pinfunction "2_2") (pintype "passive"))
      (node (ref "C9") (pin "2") (pinfunction "2_2") (pintype "passive"))
      (node (ref "J4") (pin "1") (pinfunction "GND_1") (pintype "power_in"))
      (node (ref "J4") (pin "4") (pinfunction "GND_4") (pintype "power_in"))
      (node (ref "J4") (pin "7") (pinfunction "GND_7") (pintype "power_in"))
      (node (ref "J5") (pin "1") (pinfunction "GND_1") (pintype "power_in"))
      (node (ref "J5") (pin "4") (pinfunction "GND_4") (pintype "power_in"))
      (node (ref "J5") (pin "7") (pinfunction "GND_7") (pintype "power_in"))
      (node (ref "J6") (pin "1") (pinfunction "GND_1") (pintype "power_in"))
      (node (ref "J6") (pin "4") (pinfunction "GND_4") (pintype "power_in"))
      (node (ref "J6") (pin "7") (pinfunction "GND_7") (pintype "power_in"))
      (node (ref "U1") (pin "11") (pinfunction "GND_11") (pintype "power_in"))
      (node (ref "U1") (pin "12") (pinfunction "GND_12") (pintype "power_in"))
      (node (ref "U1") (pin "13") (pinfunction "GND_13") (pintype "power_in"))
      (node (ref "U1") (pin "2") (pinfunction "DIR_2") (pintype "input"))
      (node (ref "U1") (pin "25") (pinfunction "EPAD_25") (pintype "passive"))
      (node (ref "U2") (pin "11") (pinfunction "GND_11") (pintype "power_in"))
      (node (ref "U2") (pin "12") (pinfunction "GND_12") (pintype "power_in"))
      (node (ref "U2") (pin "13") (pinfunction "GND_13") (pintype "power_in"))
      (node (ref "U2") (pin "25") (pinfunction "EPAD_25") (pintype "passive"))
      (node (ref "U3") (pin "11") (pinfunction "GND_11") (pintype "power_in"))
      (node (ref "U3") (pin "12") (pinfunction "GND_12") (pintype "power_in"))
      (node (ref "U3") (pin "13") (pinfunction "GND_13") (pintype "power_in"))
      (node (ref "U3") (pin "25") (pinfunction "EPAD_25") (pintype "passive"))
      (node (ref "U4") (pin "11") (pinfunction "GND_11") (pintype "power_in"))
      (node (ref "U4") (pin "12") (pinfunction "GND_12") (pintype "power_in"))
      (node (ref "U4") (pin "13") (pinfunction "GND_13") (pintype "power_in"))
      (node (ref "U4") (pin "25") (pinfunction "EPAD_25") (pintype "passive"))
      (node (ref "U5") (pin "11") (pinfunction "GND_11") (pintype "power_in"))
      (node (ref "U5") (pin "12") (pinfunction "GND_12") (pintype "power_in"))
      (node (ref "U5") (pin "13") (pinfunction "GND_13") (pintype "power_in"))
      (node (ref "U5") (pin "25") (pinfunction "EPAD_25") (pintype "passive"))
      (node (ref "U6") (pin "11") (pinfunction "GND_11") (pintype "power_in"))
      (node (ref "U6") (pin "12") (pinfunction "GND_12") (pintype "power_in"))
      (node (ref "U6") (pin "13") (pinfunction "GND_13") (pintype "power_in"))
      (node (ref "U6") (pin "25") (pinfunction "EPAD_25") (pintype "passive"))
      (node (ref "U7") (pin "11") (pinfunction "GND_11") (pintype "power_in"))
      (node (ref "U7") (pin "12") (pinfunction "GND_12") (pintype "power_in"))
      (node (ref "U7") (pin "13") (pinfunction "GND_13") (pintype "power_in"))
      (node (ref "U7") (pin "25") (pinfunction "EPAD_25") (pintype "passive"))
      (node (ref "U8") (pin "11") (pinfunction "GND_11") (pintype "power_in"))
      (node (ref "U8") (pin "12") (pinfunction "GND_12") (pintype "power_in"))
      (node (ref "U8") (pin "13") (pinfunction "GND_13") (pintype "power_in"))
      (node (ref "U8") (pin "25") (pinfunction "EPAD_25") (pintype "passive"))
    )
    (net (code "155") (name "VCC_3p3_CARD") (class "Default")
      (node (ref "C10") (pin "1") (pinfunction "1_1") (pintype "passive"))
      (node (ref "C11") (pin "1") (pinfunction "1_1") (pintype "passive"))
      (node (ref "C12") (pin "1") (pinfunction "1_1") (pintype "passive"))
      (node (ref "C13") (pin "1") (pinfunction "1_1") (pintype "passive"))
      (node (ref "C14") (pin "1") (pinfunction "1_1") (pintype "passive"))
      (node (ref "C15") (pin "1") (pinfunction "1_1") (pintype "passive"))
      (node (ref "C16") (pin "1") (pinfunction "1_1") (pintype "passive"))
      (node (ref "C9") (pin "1") (pinfunction "1_1") (pintype "passive"))
      (node (ref "U1") (pin "23") (pinfunction "VCCB_23") (pintype "power_in"))
      (node (ref "U1") (pin "24") (pinfunction "VCCB_24") (pintype "power_in"))
      (node (ref "U2") (pin "23") (pinfunction "VCCB_23") (pintype "power_in"))
      (node (ref "U2") (pin "24") (pinfunction "VCCB_24") (pintype "power_in"))
      (node (ref "U3") (pin "23") (pinfunction "VCCB_23") (pintype "power_in"))
      (node (ref "U3") (pin "24") (pinfunction "VCCB_24") (pintype "power_in"))
      (node (ref "U4") (pin "23") (pinfunction "VCCB_23") (pintype "power_in"))
      (node (ref "U4") (pin "24") (pinfunction "VCCB_24") (pintype "power_in"))
      (node (ref "U5") (pin "23") (pinfunction "VCCB_23") (pintype "power_in"))
      (node (ref "U5") (pin "24") (pinfunction "VCCB_24") (pintype "power_in"))
      (node (ref "U6") (pin "23") (pinfunction "VCCB_23") (pintype "power_in"))
      (node (ref "U6") (pin "24") (pinfunction "VCCB_24") (pintype "power_in"))
      (node (ref "U7") (pin "23") (pinfunction "VCCB_23") (pintype "power_in"))
      (node (ref "U7") (pin "24") (pinfunction "VCCB_24") (pintype "power_in"))
      (node (ref "U8") (pin "23") (pinfunction "VCCB_23") (pintype "power_in"))
      (node (ref "U8") (pin "24") (pinfunction "VCCB_24") (pintype "power_in"))
    )
    (net (code "156") (name "VCC_VADJ_CARD") (class "Default")
      (node (ref "C1") (pin "1") (pinfunction "1_1") (pintype "passive"))
      (node (ref "C2") (pin "1") (pinfunction "1_1") (pintype "passive"))
      (node (ref "C3") (pin "1") (pinfunction "1_1") (pintype "passive"))
      (node (ref "C4") (pin "1") (pinfunction "1_1") (pintype "passive"))
      (node (ref "C5") (pin "1") (pinfunction "1_1") (pintype "passive"))
      (node (ref "C6") (pin "1") (pinfunction "1_1") (pintype "passive"))
      (node (ref "C7") (pin "1") (pinfunction "1_1") (pintype "passive"))
      (node (ref "C8") (pin "1") (pinfunction "1_1") (pintype "passive"))
      (node (ref "U1") (pin "1") (pinfunction "VCCA_1") (pintype "power_in"))
      (node (ref "U2") (pin "1") (pinfunction "VCCA_1") (pintype "power_in"))
      (node (ref "U2") (pin "2") (pinfunction "DIR_2") (pintype "input"))
      (node (ref "U3") (pin "1") (pinfunction "VCCA_1") (pintype "power_in"))
      (node (ref "U3") (pin "2") (pinfunction "DIR_2") (pintype "input"))
      (node (ref "U4") (pin "1") (pinfunction "VCCA_1") (pintype "power_in"))
      (node (ref "U4") (pin "2") (pinfunction "DIR_2") (pintype "input"))
      (node (ref "U5") (pin "1") (pinfunction "VCCA_1") (pintype "power_in"))
      (node (ref "U5") (pin "2") (pinfunction "DIR_2") (pintype "input"))
      (node (ref "U6") (pin "1") (pinfunction "VCCA_1") (pintype "power_in"))
      (node (ref "U6") (pin "2") (pinfunction "DIR_2") (pintype "input"))
      (node (ref "U7") (pin "1") (pinfunction "VCCA_1") (pintype "power_in"))
      (node (ref "U7") (pin "2") (pinfunction "DIR_2") (pintype "input"))
      (node (ref "U8") (pin "1") (pinfunction "VCCA_1") (pintype "power_in"))
      (node (ref "U8") (pin "2") (pinfunction "DIR_2") (pintype "input"))
    )
  )
)
